# can.net
KiCad netlist of a schematic drawn in EAGLE
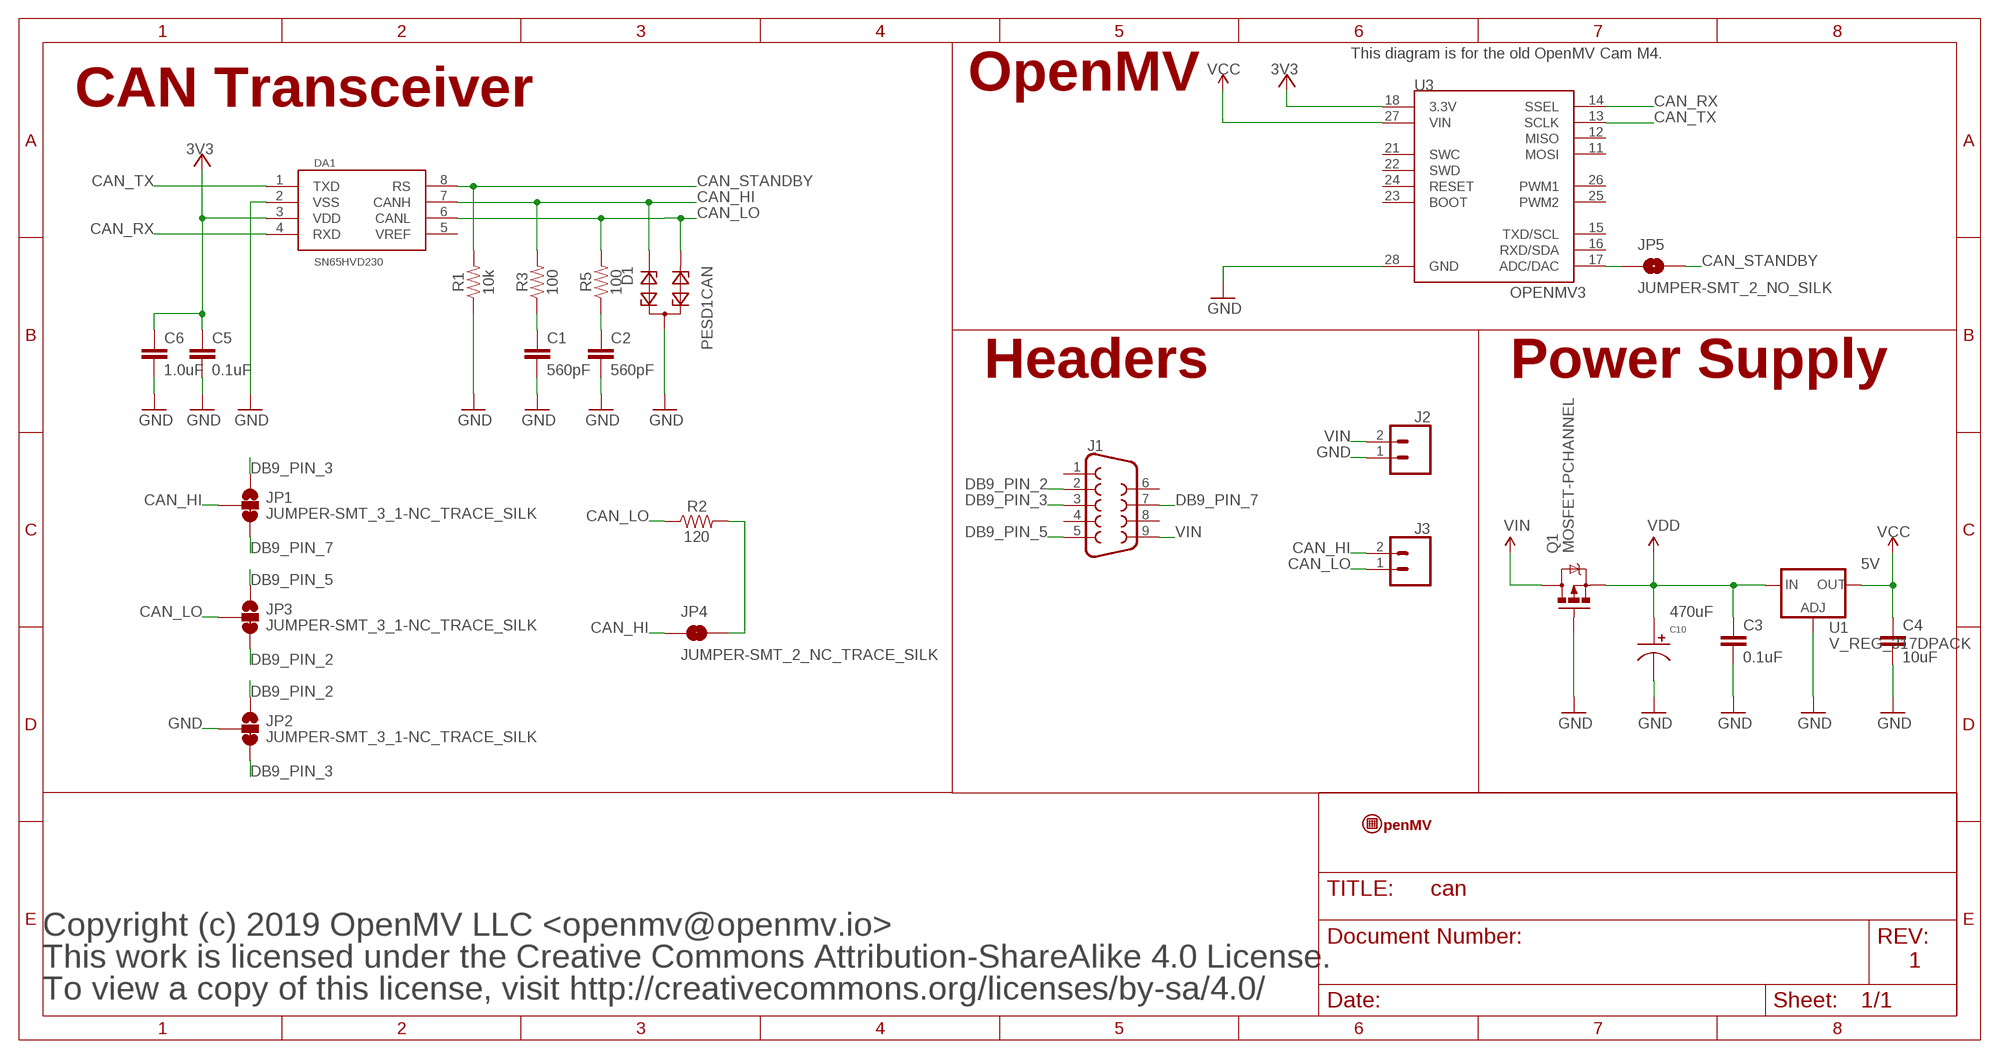
[diagram p0: schematic, sheet 1]

(export (version "E")
  (design (tool "Eeschema 10.0.6"))
  (components
    (comp (ref "C1")
      (value "560pF")
      (footprint "eagle-import:0603")
      (libsource (lib "eagle-import") (part "560PF-0603-50V-5%"))
    )
    (comp (ref "C2")
      (value "560pF")
      (footprint "eagle-import:0603")
      (libsource (lib "eagle-import") (part "560PF-0603-50V-5%"))
    )
    (comp (ref "C3")
      (value "0.1uF")
      (footprint "eagle-import:0603-CAP")
      (libsource (lib "eagle-import") (part "CAP0603-CAP"))
    )
    (comp (ref "C4")
      (value "10uF")
      (footprint "eagle-import:0805")
      (libsource (lib "eagle-import") (part "CAP0805"))
    )
    (comp (ref "C5")
      (value "0.1uF")
      (footprint "eagle-import:0603")
      (libsource (lib "eagle-import") (part "0.1UF-0603-25V-(+80/-20%)"))
    )
    (comp (ref "C6")
      (value "1.0uF")
      (footprint "eagle-import:0603")
      (libsource (lib "eagle-import") (part "1.0UF-0603-16V-10%"))
    )
    (comp (ref "C10")
      (value "CAPACITOR_P_10MM")
      (footprint "eagle-import:CP10MM")
      (libsource (lib "eagle-import") (part "CAPACITOR_P_10MM"))
    )
    (comp (ref "D1")
      (value "PESD1CAN")
      (footprint "eagle-import:SOT23")
      (libsource (lib "eagle-import") (part "PESD1CAN"))
    )
    (comp (ref "DA1")
      (value "SN65HVD230")
      (footprint "eagle-import:SO08")
      (libsource (lib "eagle-import") (part "SN65HVD230"))
    )
    (comp (ref "J1")
      (value "DB9MALE")
      (footprint "eagle-import:DB9_MALE")
      (libsource (lib "eagle-import") (part "DB9MALE"))
    )
    (comp (ref "J2")
      (value "CONN_02")
      (footprint "eagle-import:1X02")
      (libsource (lib "eagle-import") (part "CONN_02"))
    )
    (comp (ref "J3")
      (value "CONN_02")
      (footprint "eagle-import:1X02")
      (libsource (lib "eagle-import") (part "CONN_02"))
    )
    (comp (ref "JP1")
      (value "JUMPER-SMT_3_1-NC_TRACE_SILK")
      (footprint "eagle-import:SMT-JUMPER_3_1-NC_TRACE_SILK")
      (libsource (lib "eagle-import") (part "JUMPER-SMT_3_1-NC_TRACE_SILK"))
    )
    (comp (ref "JP2")
      (value "JUMPER-SMT_3_1-NC_TRACE_SILK")
      (footprint "eagle-import:SMT-JUMPER_3_1-NC_TRACE_SILK")
      (libsource (lib "eagle-import") (part "JUMPER-SMT_3_1-NC_TRACE_SILK"))
    )
    (comp (ref "JP3")
      (value "JUMPER-SMT_3_1-NC_TRACE_SILK")
      (footprint "eagle-import:SMT-JUMPER_3_1-NC_TRACE_SILK")
      (libsource (lib "eagle-import") (part "JUMPER-SMT_3_1-NC_TRACE_SILK"))
    )
    (comp (ref "JP4")
      (value "JUMPER-SMT_2_NC_TRACE_SILK")
      (footprint "eagle-import:SMT-JUMPER_2_NC_TRACE_SILK")
      (libsource (lib "eagle-import") (part "JUMPER-SMT_2_NC_TRACE_SILK"))
    )
    (comp (ref "JP5")
      (value "JUMPER-SMT_2_NO_SILK")
      (footprint "eagle-import:SMT-JUMPER_2_NO_SILK")
      (libsource (lib "eagle-import") (part "JUMPER-SMT_2_NO_SILK"))
    )
    (comp (ref "Q1")
      (value "MOSFET-PCHANNEL")
      (footprint "eagle-import:SOT23-3")
      (libsource (lib "eagle-import") (part "MOSFET-PCHANNEL"))
    )
    (comp (ref "R1")
      (value "10k")
      (footprint "eagle-import:0603")
      (libsource (lib "eagle-import") (part "10KOHM-0603-1/10W-1%"))
    )
    (comp (ref "R2")
      (value "120")
      (footprint "eagle-import:0603")
      (libsource (lib "eagle-import") (part "100OHM-0603-1/10W-1%"))
    )
    (comp (ref "R3")
      (value "100")
      (footprint "eagle-import:0603")
      (libsource (lib "eagle-import") (part "100OHM-0603-1/10W-1%"))
    )
    (comp (ref "R5")
      (value "100")
      (footprint "eagle-import:0603")
      (libsource (lib "eagle-import") (part "100OHM-0603-1/10W-1%"))
    )
    (comp (ref "U$9")
      (value "OPENMV-LOGO")
      (footprint "eagle-import:OPENMV-LOGO")
      (libsource (lib "eagle-import") (part "OPENMV-LOGO"))
    )
    (comp (ref "U1")
      (value "V_REG_317DPACK")
      (footprint "eagle-import:V-REG_DPACK")
      (libsource (lib "eagle-import") (part "V_REG_317DPACK"))
    )
    (comp (ref "U3")
      (value "OPENMV3")
      (footprint "eagle-import:OPENMV3")
      (libsource (lib "eagle-import") (part "OPENMV3"))
    )
  )
  (nets
    (net (code "1") (name "/CAN_HI") (class "Default")
      (node (ref "D1") (pin "1") (pinfunction "1_1") (pintype "passive"))
      (node (ref "DA1") (pin "7") (pinfunction "CANH_7") (pintype "bidirectional"))
      (node (ref "J3") (pin "2") (pinfunction "2_2") (pintype "passive"))
      (node (ref "JP1") (pin "2") (pinfunction "2_2") (pintype "passive"))
      (node (ref "JP4") (pin "1") (pinfunction "1_1") (pintype "passive"))
      (node (ref "R3") (pin "2") (pinfunction "2_2") (pintype "passive"))
    )
    (net (code "2") (name "/CAN_LO") (class "Default")
      (node (ref "D1") (pin "2") (pinfunction "2_2") (pintype "passive"))
      (node (ref "DA1") (pin "6") (pinfunction "CANL_6") (pintype "bidirectional"))
      (node (ref "J3") (pin "1") (pinfunction "1_1") (pintype "passive"))
      (node (ref "JP3") (pin "2") (pinfunction "2_2") (pintype "passive"))
      (node (ref "R2") (pin "1") (pinfunction "1_1") (pintype "passive"))
      (node (ref "R5") (pin "2") (pinfunction "2_2") (pintype "passive"))
    )
    (net (code "3") (name "/CAN_RX") (class "Default")
      (node (ref "DA1") (pin "4") (pinfunction "RXD_4") (pintype "output"))
      (node (ref "U3") (pin "14") (pinfunction "SSEL_14") (pintype "bidirectional"))
    )
    (net (code "4") (name "/CAN_STANDBY") (class "Default")
      (node (ref "DA1") (pin "8") (pinfunction "RS_8") (pintype "input"))
      (node (ref "JP5") (pin "2") (pinfunction "2_2") (pintype "passive"))
      (node (ref "R1") (pin "2") (pinfunction "2_2") (pintype "passive"))
    )
    (net (code "5") (name "/CAN_TX") (class "Default")
      (node (ref "DA1") (pin "1") (pinfunction "TXD_1") (pintype "input"))
      (node (ref "U3") (pin "13") (pinfunction "SCLK_13") (pintype "bidirectional"))
    )
    (net (code "6") (name "/DB9_PIN_2") (class "Default")
      (node (ref "J1") (pin "2") (pinfunction "2_2") (pintype "passive"))
      (node (ref "JP2") (pin "1") (pinfunction "1_1") (pintype "passive"))
      (node (ref "JP3") (pin "3") (pinfunction "3_3") (pintype "passive"))
    )
    (net (code "7") (name "/DB9_PIN_3") (class "Default")
      (node (ref "J1") (pin "3") (pinfunction "3_3") (pintype "passive"))
      (node (ref "JP1") (pin "1") (pinfunction "1_1") (pintype "passive"))
      (node (ref "JP2") (pin "3") (pinfunction "3_3") (pintype "passive"))
    )
    (net (code "8") (name "/DB9_PIN_5") (class "Default")
      (node (ref "J1") (pin "5") (pinfunction "5_5") (pintype "passive"))
      (node (ref "JP3") (pin "1") (pinfunction "1_1") (pintype "passive"))
    )
    (net (code "9") (name "/DB9_PIN_7") (class "Default")
      (node (ref "J1") (pin "7") (pinfunction "7_7") (pintype "passive"))
      (node (ref "JP1") (pin "3") (pinfunction "3_3") (pintype "passive"))
    )
    (net (code "10") (name "3V3") (class "Default")
      (node (ref "C5") (pin "1") (pinfunction "1_1") (pintype "passive"))
      (node (ref "C6") (pin "1") (pinfunction "1_1") (pintype "passive"))
      (node (ref "DA1") (pin "3") (pinfunction "VDD_3") (pintype "power_in"))
      (node (ref "U3") (pin "18") (pinfunction "3.3V_18") (pintype "power_in"))
    )
    (net (code "11") (name "GND") (class "Default")
      (node (ref "C1") (pin "2") (pinfunction "2_2") (pintype "passive"))
      (node (ref "C10") (pin "P$2") (pinfunction "P$2_P$2") (pintype "passive"))
      (node (ref "C2") (pin "2") (pinfunction "2_2") (pintype "passive"))
      (node (ref "C3") (pin "2") (pinfunction "2_2") (pintype "passive"))
      (node (ref "C4") (pin "2") (pinfunction "2_2") (pintype "passive"))
      (node (ref "C5") (pin "2") (pinfunction "2_2") (pintype "passive"))
      (node (ref "C6") (pin "2") (pinfunction "2_2") (pintype "passive"))
      (node (ref "D1") (pin "3") (pinfunction "3_3") (pintype "passive"))
      (node (ref "DA1") (pin "2") (pinfunction "VSS_2") (pintype "power_in"))
      (node (ref "J2") (pin "1") (pinfunction "1_1") (pintype "passive"))
      (node (ref "JP2") (pin "2") (pinfunction "2_2") (pintype "passive"))
      (node (ref "Q1") (pin "1") (pinfunction "G_1") (pintype "passive"))
      (node (ref "R1") (pin "1") (pinfunction "1_1") (pintype "passive"))
      (node (ref "U1") (pin "1") (pinfunction "ADJ_1") (pintype "input"))
      (node (ref "U3") (pin "28") (pinfunction "GND_28") (pintype "power_in"))
    )
    (net (code "12") (name "Net-(C1-Pad1)") (class "Default")
      (node (ref "C1") (pin "1") (pinfunction "1_1") (pintype "passive"))
      (node (ref "R3") (pin "1") (pinfunction "1_1") (pintype "passive"))
    )
    (net (code "13") (name "Net-(C2-Pad1)") (class "Default")
      (node (ref "C2") (pin "1") (pinfunction "1_1") (pintype "passive"))
      (node (ref "R5") (pin "1") (pinfunction "1_1") (pintype "passive"))
    )
    (net (code "14") (name "Net-(JP4-Pad2)") (class "Default")
      (node (ref "JP4") (pin "2") (pinfunction "2_2") (pintype "passive"))
      (node (ref "R2") (pin "2") (pinfunction "2_2") (pintype "passive"))
    )
    (net (code "15") (name "Net-(U3-ADC{slash}DAC)") (class "Default")
      (node (ref "JP5") (pin "1") (pinfunction "1_1") (pintype "passive"))
      (node (ref "U3") (pin "17") (pinfunction "ADC/DAC_17") (pintype "bidirectional"))
    )
    (net (code "16") (name "VCC") (class "Default")
      (node (ref "C4") (pin "1") (pinfunction "1_1") (pintype "passive"))
      (node (ref "U1") (pin "4") (pinfunction "OUT_4") (pintype "output"))
      (node (ref "U3") (pin "27") (pinfunction "VIN_27") (pintype "power_in"))
    )
    (net (code "17") (name "VDD") (class "Default")
      (node (ref "C10") (pin "P$1") (pinfunction "P$1_P$1") (pintype "passive"))
      (node (ref "C3") (pin "1") (pinfunction "1_1") (pintype "passive"))
      (node (ref "Q1") (pin "2") (pinfunction "S_2") (pintype "passive"))
      (node (ref "U1") (pin "3") (pinfunction "IN_3") (pintype "input"))
    )
    (net (code "18") (name "VIN") (class "Default")
      (node (ref "J1") (pin "9") (pinfunction "9_9") (pintype "passive"))
      (node (ref "J2") (pin "2") (pinfunction "2_2") (pintype "passive"))
      (node (ref "Q1") (pin "3") (pinfunction "D_3") (pintype "passive"))
    )
    (net (code "19") (name "unconnected-(DA1-VREF-Pad5)") (class "Default")
      (node (ref "DA1") (pin "5") (pinfunction "VREF_5") (pintype "passive"))
    )
    (net (code "20") (name "unconnected-(J1-Pad1)") (class "Default")
      (node (ref "J1") (pin "1") (pinfunction "1_1") (pintype "passive"))
    )
    (net (code "21") (name "unconnected-(J1-Pad4)") (class "Default")
      (node (ref "J1") (pin "4") (pinfunction "4_4") (pintype "passive"))
    )
    (net (code "22") (name "unconnected-(J1-Pad6)") (class "Default")
      (node (ref "J1") (pin "6") (pinfunction "6_6") (pintype "passive"))
    )
    (net (code "23") (name "unconnected-(J1-Pad8)") (class "Default")
      (node (ref "J1") (pin "8") (pinfunction "8_8") (pintype "passive"))
    )
    (net (code "24") (name "unconnected-(U3-BOOT-Pad23)") (class "Default")
      (node (ref "U3") (pin "23") (pinfunction "BOOT_23") (pintype "bidirectional"))
    )
    (net (code "25") (name "unconnected-(U3-MISO-Pad12)") (class "Default")
      (node (ref "U3") (pin "12") (pinfunction "MISO_12") (pintype "bidirectional"))
    )
    (net (code "26") (name "unconnected-(U3-MOSI-Pad11)") (class "Default")
      (node (ref "U3") (pin "11") (pinfunction "MOSI_11") (pintype "bidirectional"))
    )
    (net (code "27") (name "unconnected-(U3-PWM1-Pad26)") (class "Default")
      (node (ref "U3") (pin "26") (pinfunction "PWM1_26") (pintype "bidirectional"))
    )
    (net (code "28") (name "unconnected-(U3-PWM2-Pad25)") (class "Default")
      (node (ref "U3") (pin "25") (pinfunction "PWM2_25") (pintype "bidirectional"))
    )
    (net (code "29") (name "unconnected-(U3-RESET-Pad24)") (class "Default")
      (node (ref "U3") (pin "24") (pinfunction "RESET_24") (pintype "bidirectional"))
    )
    (net (code "30") (name "unconnected-(U3-RXD{slash}SDA-Pad16)") (class "Default")
      (node (ref "U3") (pin "16") (pinfunction "RXD/SDA_16") (pintype "bidirectional"))
    )
    (net (code "31") (name "unconnected-(U3-SWC-Pad21)") (class "Default")
      (node (ref "U3") (pin "21") (pinfunction "SWC_21") (pintype "bidirectional"))
    )
    (net (code "32") (name "unconnected-(U3-SWD-Pad22)") (class "Default")
      (node (ref "U3") (pin "22") (pinfunction "SWD_22") (pintype "bidirectional"))
    )
    (net (code "33") (name "unconnected-(U3-TXD{slash}SCL-Pad15)") (class "Default")
      (node (ref "U3") (pin "15") (pinfunction "TXD/SCL_15") (pintype "bidirectional"))
    )
  )
)
